# RFHeader.net
KiCad netlist of a schematic drawn in Altium Designer
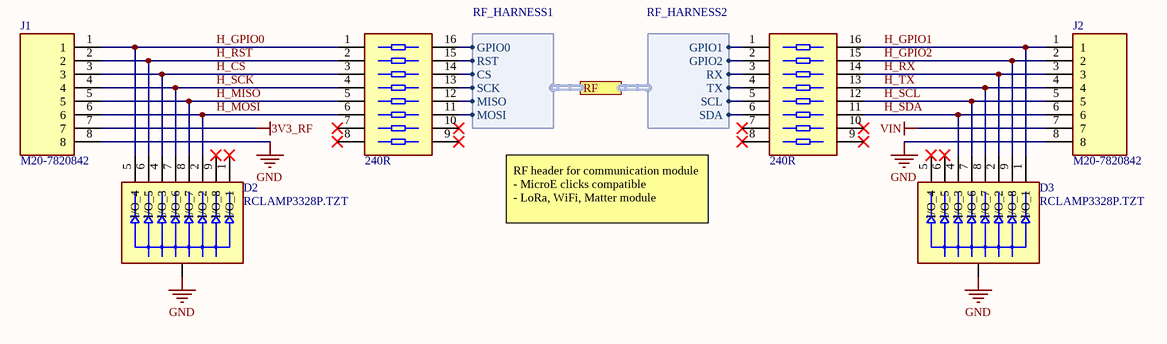
[diagram p0: RFHeader.SchDoc]

(export (version "E")
  (design (tool "Eeschema 10.0.6"))
  (components
    (comp (ref "D2")
      (value "RCLAMP3328P.TZT")
      (footprint "SamacSys:RCLAMP3328PTZT")
      (description "TVS Diode (Uni-directional)")
      (fields (field (name "MOUSER PART NUMBER") "947-RCLAMP3328P.TZT"))
      (libsource (lib "SamacSys") (part "RCLAMP3328P.TZT"))
    )
    (comp (ref "D3")
      (value "RCLAMP3328P.TZT")
      (footprint "SamacSys:RCLAMP3328PTZT")
      (description "TVS Diode (Uni-directional)")
      (fields (field (name "MOUSER PART NUMBER") "947-RCLAMP3328P.TZT"))
      (libsource (lib "SamacSys") (part "RCLAMP3328P.TZT"))
    )
    (comp (ref "J1")
      (value "M20-7820842")
      (footprint "SamacSys:RHDR8W80P0X254_1X8_2032X254X850P")
      (description "Connector")
      (fields (field (name "MOUSER PART NUMBER") "855-M20-7820842"))
      (libsource (lib "*") (part "M20-7820842"))
    )
    (comp (ref "J2")
      (value "M20-7820842")
      (footprint "SamacSys:RHDR8W80P0X254_1X8_2032X254X850P")
      (description "Connector")
      (fields (field (name "MOUSER PART NUMBER") "855-M20-7820842"))
      (libsource (lib "") (part "M20-7820842_1"))
    )
    (comp (ref "RN1")
      (value "240R")
      (footprint "SamacSys:EXBU2H")
      (description "Resistor Network (16-Pin)")
      (fields
        (field (name "MANUFACTURER_PART_NUMBER") "EXB-U2H102JV")
        (field (name "MOUSER PART NUMBER") "667-EXB-U2H102JV")
      )
      (libsource (lib "SamacSys") (part "EXB-U2H102JV"))
    )
    (comp (ref "RN2")
      (value "240R")
      (footprint "SamacSys:EXBU2H")
      (description "Resistor Network (16-Pin)")
      (fields
        (field (name "MANUFACTURER_PART_NUMBER") "EXB-U2H102JV")
        (field (name "MOUSER PART NUMBER") "667-EXB-U2H102JV")
      )
      (libsource (lib "SamacSys") (part "EXB-U2H102JV"))
    )
  )
  (nets
    (net (code "2") (name "/CS") (class "Default")
      (node (ref "RN1") (pin "14") (pinfunction "14_14") (pintype "passive"))
    )
    (net (code "3") (name "/GPIO0") (class "Default")
      (node (ref "RN1") (pin "16") (pinfunction "16_16") (pintype "passive"))
    )
    (net (code "4") (name "/GPIO1") (class "Default")
      (node (ref "RN2") (pin "1") (pinfunction "1_1") (pintype "passive"))
    )
    (net (code "5") (name "/GPIO2") (class "Default")
      (node (ref "RN2") (pin "2") (pinfunction "2_2") (pintype "passive"))
    )
    (net (code "6") (name "/H_CS") (class "Default")
      (node (ref "D2") (pin "4") (pinfunction "I/O_3_4") (pintype "passive"))
      (node (ref "J1") (pin "3") (pinfunction "3_3") (pintype "passive"))
      (node (ref "RN1") (pin "3") (pinfunction "3_3") (pintype "passive"))
    )
    (net (code "7") (name "/H_GPIO0") (class "Default")
      (node (ref "D2") (pin "5") (pinfunction "I/O_4_5") (pintype "passive"))
      (node (ref "J1") (pin "1") (pinfunction "1_1") (pintype "passive"))
      (node (ref "RN1") (pin "1") (pinfunction "1_1") (pintype "passive"))
    )
    (net (code "8") (name "/H_GPIO1") (class "Default")
      (node (ref "D3") (pin "1") (pinfunction "I/O_1_1") (pintype "passive"))
      (node (ref "J2") (pin "1") (pinfunction "1_1") (pintype "passive"))
      (node (ref "RN2") (pin "16") (pinfunction "16_16") (pintype "passive"))
    )
    (net (code "9") (name "/H_GPIO2") (class "Default")
      (node (ref "D3") (pin "9") (pinfunction "I/O_8_9") (pintype "passive"))
      (node (ref "J2") (pin "2") (pinfunction "2_2") (pintype "passive"))
      (node (ref "RN2") (pin "15") (pinfunction "15_15") (pintype "passive"))
    )
    (net (code "10") (name "/H_MISO") (class "Default")
      (node (ref "D2") (pin "8") (pinfunction "I/O_7_8") (pintype "passive"))
      (node (ref "J1") (pin "5") (pinfunction "5_5") (pintype "passive"))
      (node (ref "RN1") (pin "5") (pinfunction "5_5") (pintype "passive"))
    )
    (net (code "11") (name "/H_MOSI") (class "Default")
      (node (ref "D2") (pin "2") (pinfunction "I/O_2_2") (pintype "passive"))
      (node (ref "J1") (pin "6") (pinfunction "6_6") (pintype "passive"))
      (node (ref "RN1") (pin "6") (pinfunction "6_6") (pintype "passive"))
    )
    (net (code "12") (name "/H_RST") (class "Default")
      (node (ref "D2") (pin "6") (pinfunction "I/O_5_6") (pintype "passive"))
      (node (ref "J1") (pin "2") (pinfunction "2_2") (pintype "passive"))
      (node (ref "RN1") (pin "2") (pinfunction "2_2") (pintype "passive"))
    )
    (net (code "13") (name "/H_RX") (class "Default")
      (node (ref "D3") (pin "2") (pinfunction "I/O_2_2") (pintype "passive"))
      (node (ref "J2") (pin "3") (pinfunction "3_3") (pintype "passive"))
      (node (ref "RN2") (pin "14") (pinfunction "14_14") (pintype "passive"))
    )
    (net (code "14") (name "/H_SCK") (class "Default")
      (node (ref "D2") (pin "7") (pinfunction "I/O_6_7") (pintype "passive"))
      (node (ref "J1") (pin "4") (pinfunction "4_4") (pintype "passive"))
      (node (ref "RN1") (pin "4") (pinfunction "4_4") (pintype "passive"))
    )
    (net (code "15") (name "/H_SCL") (class "Default")
      (node (ref "D3") (pin "7") (pinfunction "I/O_6_7") (pintype "passive"))
      (node (ref "J2") (pin "5") (pinfunction "5_5") (pintype "passive"))
      (node (ref "RN2") (pin "12") (pinfunction "12_12") (pintype "passive"))
    )
    (net (code "16") (name "/H_SDA") (class "Default")
      (node (ref "D3") (pin "4") (pinfunction "I/O_3_4") (pintype "passive"))
      (node (ref "J2") (pin "6") (pinfunction "6_6") (pintype "passive"))
      (node (ref "RN2") (pin "11") (pinfunction "11_11") (pintype "passive"))
    )
    (net (code "17") (name "/H_TX") (class "Default")
      (node (ref "D3") (pin "8") (pinfunction "I/O_7_8") (pintype "passive"))
      (node (ref "J2") (pin "4") (pinfunction "4_4") (pintype "passive"))
      (node (ref "RN2") (pin "13") (pinfunction "13_13") (pintype "passive"))
    )
    (net (code "18") (name "/MISO") (class "Default")
      (node (ref "RN1") (pin "12") (pinfunction "12_12") (pintype "passive"))
    )
    (net (code "19") (name "/MOSI") (class "Default")
      (node (ref "RN1") (pin "11") (pinfunction "11_11") (pintype "passive"))
    )
    (net (code "20") (name "/RST") (class "Default")
      (node (ref "RN1") (pin "15") (pinfunction "15_15") (pintype "passive"))
    )
    (net (code "21") (name "/RX") (class "Default")
      (node (ref "RN2") (pin "3") (pinfunction "3_3") (pintype "passive"))
    )
    (net (code "22") (name "/SCK") (class "Default")
      (node (ref "RN1") (pin "13") (pinfunction "13_13") (pintype "passive"))
    )
    (net (code "23") (name "/SCL") (class "Default")
      (node (ref "RN2") (pin "5") (pinfunction "5_5") (pintype "passive"))
    )
    (net (code "24") (name "/SDA") (class "Default")
      (node (ref "RN2") (pin "6") (pinfunction "6_6") (pintype "passive"))
    )
    (net (code "25") (name "/TX") (class "Default")
      (node (ref "RN2") (pin "4") (pinfunction "4_4") (pintype "passive"))
    )
    (net (code "27") (name "3V3_RF") (class "Default")
      (node (ref "J1") (pin "7") (pinfunction "7_7") (pintype "passive"))
    )
    (net (code "28") (name "GND") (class "Default")
      (node (ref "D2") (pin "3") (pinfunction "GND_3") (pintype "passive"))
      (node (ref "D3") (pin "3") (pinfunction "GND_3") (pintype "passive"))
      (node (ref "J1") (pin "8") (pinfunction "8_8") (pintype "passive"))
      (node (ref "J2") (pin "8") (pinfunction "8_8") (pintype "passive"))
    )
    (net (code "29") (name "VIN") (class "Default")
      (node (ref "J2") (pin "7") (pinfunction "7_7") (pintype "passive"))
    )
    (net (code "30") (name "unconnected-(D2-I{slash}O_1-Pad1)") (class "Default")
      (node (ref "D2") (pin "1") (pinfunction "I/O_1_1") (pintype "passive+no_connect"))
    )
    (net (code "31") (name "unconnected-(D2-I{slash}O_8-Pad9)") (class "Default")
      (node (ref "D2") (pin "9") (pinfunction "I/O_8_9") (pintype "passive+no_connect"))
    )
    (net (code "32") (name "unconnected-(D3-I{slash}O_4-Pad5)") (class "Default")
      (node (ref "D3") (pin "5") (pinfunction "I/O_4_5") (pintype "passive+no_connect"))
    )
    (net (code "33") (name "unconnected-(D3-I{slash}O_5-Pad6)") (class "Default")
      (node (ref "D3") (pin "6") (pinfunction "I/O_5_6") (pintype "passive+no_connect"))
    )
    (net (code "34") (name "unconnected-(RN1-Pad7)") (class "Default")
      (node (ref "RN1") (pin "7") (pinfunction "7_7") (pintype "passive+no_connect"))
    )
    (net (code "35") (name "unconnected-(RN1-Pad8)") (class "Default")
      (node (ref "RN1") (pin "8") (pinfunction "8_8") (pintype "passive+no_connect"))
    )
    (net (code "36") (name "unconnected-(RN1-Pad9)") (class "Default")
      (node (ref "RN1") (pin "9") (pinfunction "9_9") (pintype "passive+no_connect"))
    )
    (net (code "37") (name "unconnected-(RN1-Pad10)") (class "Default")
      (node (ref "RN1") (pin "10") (pinfunction "10_10") (pintype "passive+no_connect"))
    )
    (net (code "38") (name "unconnected-(RN2-Pad7)") (class "Default")
      (node (ref "RN2") (pin "7") (pinfunction "7_7") (pintype "passive+no_connect"))
    )
    (net (code "39") (name "unconnected-(RN2-Pad8)") (class "Default")
      (node (ref "RN2") (pin "8") (pinfunction "8_8") (pintype "passive+no_connect"))
    )
    (net (code "40") (name "unconnected-(RN2-Pad9)") (class "Default")
      (node (ref "RN2") (pin "9") (pinfunction "9_9") (pintype "passive+no_connect"))
    )
    (net (code "41") (name "unconnected-(RN2-Pad10)") (class "Default")
      (node (ref "RN2") (pin "10") (pinfunction "10_10") (pintype "passive+no_connect"))
    )
  )
)
